# transistor_current_source.net
KiCad netlist of a schematic drawn in EAGLE
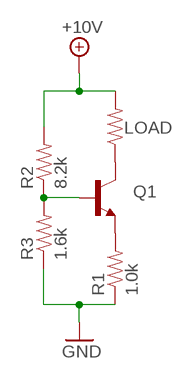
[diagram p0: schematic, sheet 1]

(export (version "E")
  (design (tool "Eeschema 10.0.6"))
  (components
    (comp (ref "LOAD")
      (value "RESISTOR0402-RES")
      (footprint "eagle-import:0402-RES")
      (libsource (lib "eagle-import") (part "RESISTOR0402-RES"))
    )
    (comp (ref "Q1")
      (value "TRANSISTOR_NPN\"")
      (footprint "eagle-import:SOT223")
      (libsource (lib "eagle-import") (part "TRANSISTOR_NPN{dblquote}"))
    )
    (comp (ref "R1")
      (value "1.0k")
      (footprint "eagle-import:0402-RES")
      (libsource (lib "eagle-import") (part "RESISTOR0402-RES"))
    )
    (comp (ref "R2")
      (value "8.2k")
      (footprint "eagle-import:0402-RES")
      (libsource (lib "eagle-import") (part "RESISTOR0402-RES"))
    )
    (comp (ref "R3")
      (value "1.6k")
      (footprint "eagle-import:0402-RES")
      (libsource (lib "eagle-import") (part "RESISTOR0402-RES"))
    )
  )
  (nets
    (net (code "1") (name "+10V") (class "Default")
      (node (ref "LOAD") (pin "2") (pinfunction "2_2") (pintype "passive"))
      (node (ref "R2") (pin "2") (pinfunction "2_2") (pintype "passive"))
    )
    (net (code "2") (name "GND") (class "Default")
      (node (ref "R1") (pin "1") (pinfunction "1_1") (pintype "passive"))
      (node (ref "R3") (pin "1") (pinfunction "1_1") (pintype "passive"))
    )
    (net (code "3") (name "Net-(Q1-B)") (class "Default")
      (node (ref "Q1") (pin "1") (pinfunction "B_1") (pintype "passive"))
      (node (ref "R2") (pin "1") (pinfunction "1_1") (pintype "passive"))
      (node (ref "R3") (pin "2") (pinfunction "2_2") (pintype "passive"))
    )
    (net (code "4") (name "Net-(Q1-C)") (class "Default")
      (node (ref "LOAD") (pin "1") (pinfunction "1_1") (pintype "passive"))
      (node (ref "Q1") (pin "2") (pinfunction "C_2") (pintype "passive"))
    )
    (net (code "5") (name "Net-(Q1-E)") (class "Default")
      (node (ref "Q1") (pin "3") (pinfunction "E_3") (pintype "passive"))
      (node (ref "R1") (pin "2") (pinfunction "2_2") (pintype "passive"))
    )
  )
)
